# Microcontroller.net
KiCad netlist of a schematic drawn in Altium Designer
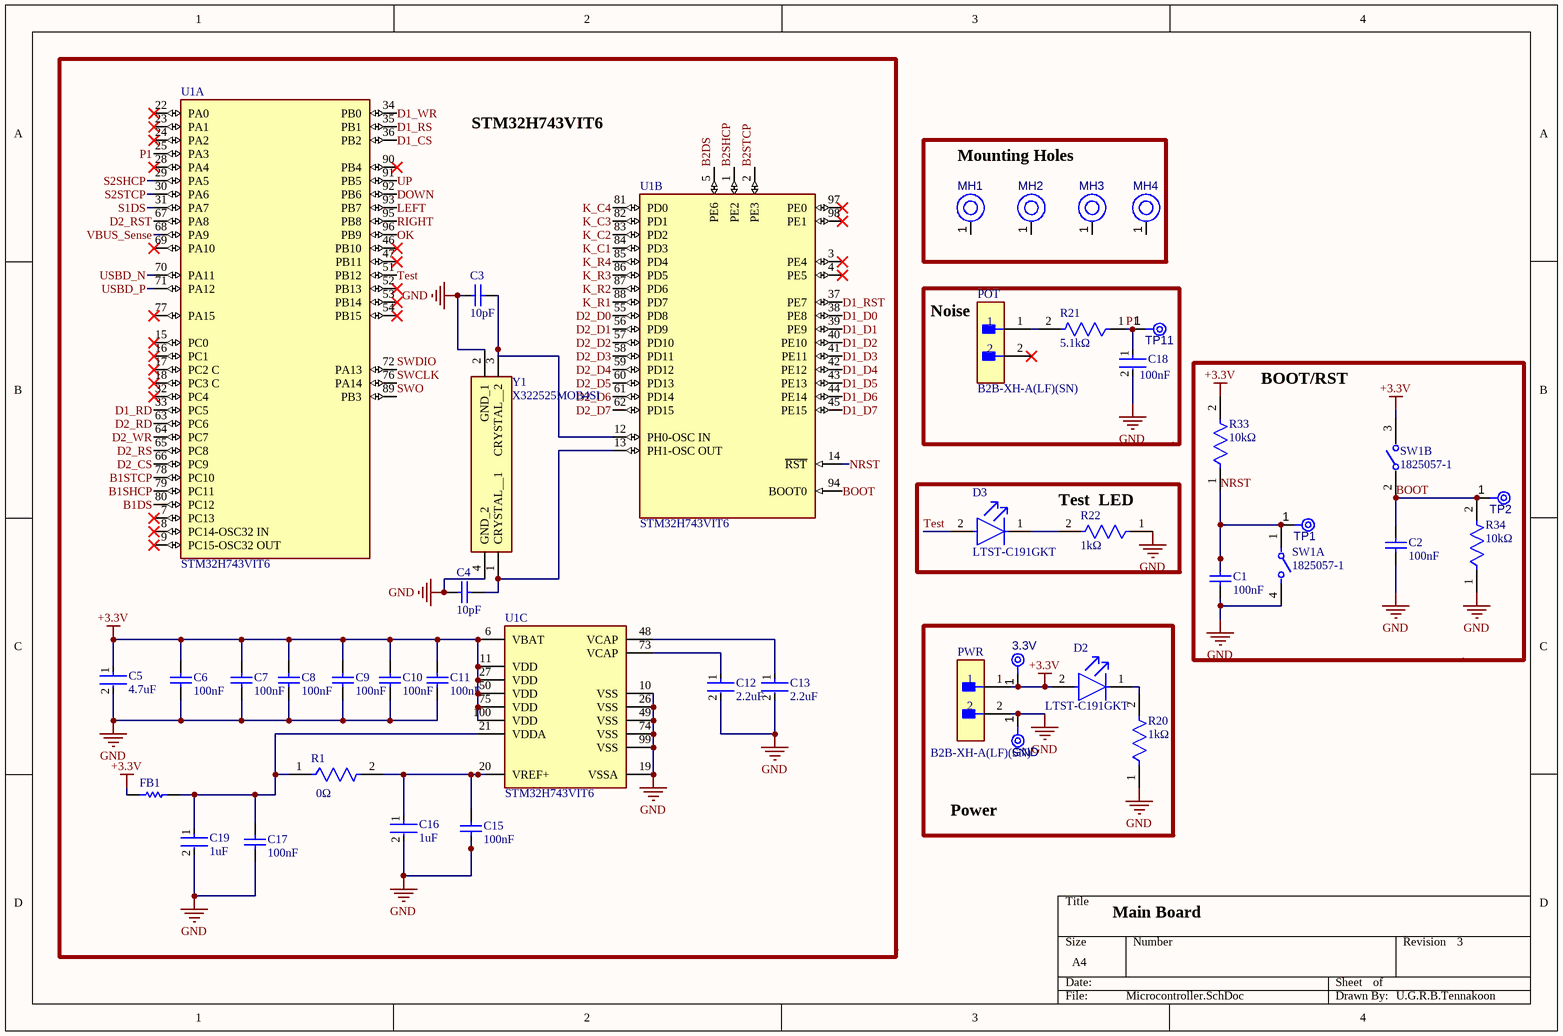
[diagram p0: Microcontroller.SchDoc]

(export (version "E")
  (design (tool "Eeschema 10.0.6"))
  (components
    (comp (ref "3.3V")
      (value "TPAD6R")
      (footprint "TP06R")
      (description "0.6mm round")
      (libsource (lib "ravindu tennakoon") (part "CMP-001-0001-4"))
    )
    (comp (ref "C1")
      (value "100nF")
      (footprint "CAPC1050X55X23ML05T13")
      (description "Chip Capacitor, 100 nF, +/- 10%, 16 V, -55 to 125 degC, 0402 (1005 Metric), RoHS, Tape and Reel")
      (fields (field (name "MANUFACTURER") "Samsung Electro-Mechanics"))
      (libsource (lib "Altium Content Vault") (part "CAP-NP-2"))
    )
    (comp (ref "C2")
      (value "100nF")
      (footprint "CAPC1050X55X23ML05T13")
      (description "Chip Capacitor, 100 nF, +/- 10%, 16 V, -55 to 125 degC, 0402 (1005 Metric), RoHS, Tape and Reel")
      (fields (field (name "MANUFACTURER") "Samsung Electro-Mechanics"))
      (libsource (lib "Altium Content Vault") (part "CAP-NP-2"))
    )
    (comp (ref "C3")
      (value "10pF")
      (footprint "CAPC1050X55X23ML05T13")
      (fields (field (name "MANUFACTURER") "Samsung Electro-Mechanics"))
      (libsource (lib "Altium Content Vault") (part "CAP-NP-2"))
    )
    (comp (ref "C4")
      (value "10pF")
      (footprint "CAPC1050X55X23ML05T13")
      (fields (field (name "MANUFACTURER") "Samsung Electro-Mechanics"))
      (libsource (lib "Altium Content Vault") (part "CAP-NP-2"))
    )
    (comp (ref "C5")
      (value "4.7uF")
      (footprint "FP-CC0603-DA-MFG")
      (description "CC0603KRX5R8BB475 CAP CER 4.7UF 25V X5R 0603")
      (fields
        (field (name "MANUFACTURER") "YAGEO")
        (field (name "MANUFACTURER PART NUMBER") "CC0603KRX5R8BB475")
      )
      (libsource (lib "Altium Content Vault") (part "11868f565c42a9108669ba33697ecf6"))
    )
    (comp (ref "C6")
      (value "100nF")
      (footprint "CAPC1050X55X23ML05T13")
      (fields (field (name "MANUFACTURER") "Samsung Electro-Mechanics"))
      (libsource (lib "Altium Content Vault") (part "CAP-NP-2"))
    )
    (comp (ref "C7")
      (value "100nF")
      (footprint "CAPC1050X55X23ML05T13")
      (description "Chip Capacitor, 100 nF, +/- 10%, 16 V, -55 to 125 degC, 0402 (1005 Metric), RoHS, Tape and Reel")
      (fields (field (name "MANUFACTURER") "Samsung Electro-Mechanics"))
      (libsource (lib "Altium Content Vault") (part "CAP-NP-2"))
    )
    (comp (ref "C8")
      (value "100nF")
      (footprint "CAPC1050X55X23ML05T13")
      (description "Chip Capacitor, 100 nF, +/- 10%, 16 V, -55 to 125 degC, 0402 (1005 Metric), RoHS, Tape and Reel")
      (fields (field (name "MANUFACTURER") "Samsung Electro-Mechanics"))
      (libsource (lib "Altium Content Vault") (part "CAP-NP-2"))
    )
    (comp (ref "C9")
      (value "100nF")
      (footprint "CAPC1050X55X23ML05T13")
      (description "Chip Capacitor, 100 nF, +/- 10%, 16 V, -55 to 125 degC, 0402 (1005 Metric), RoHS, Tape and Reel")
      (fields (field (name "MANUFACTURER") "Samsung Electro-Mechanics"))
      (libsource (lib "Altium Content Vault") (part "CAP-NP-2"))
    )
    (comp (ref "C10")
      (value "100nF")
      (footprint "CAPC1050X55X23ML05T13")
      (description "Chip Capacitor, 100 nF, +/- 10%, 16 V, -55 to 125 degC, 0402 (1005 Metric), RoHS, Tape and Reel")
      (fields (field (name "MANUFACTURER") "Samsung Electro-Mechanics"))
      (libsource (lib "Altium Content Vault") (part "CAP-NP-2"))
    )
    (comp (ref "C11")
      (value "100nF")
      (footprint "CAPC1050X55X23ML05T13")
      (description "Chip Capacitor, 100 nF, +/- 10%, 16 V, -55 to 125 degC, 0402 (1005 Metric), RoHS, Tape and Reel")
      (fields (field (name "MANUFACTURER") "Samsung Electro-Mechanics"))
      (libsource (lib "Altium Content Vault") (part "CAP-NP-2"))
    )
    (comp (ref "C12")
      (value "2.2uF")
      (footprint "FP-CL10-IPC_A")
      (description "CL10A225KO8NNNC Cap Ceramic 2.2uF 16V X5R ±10% Pad SMD 0603 +85°C T/R")
      (fields (field (name "TOLERANCE") "10%") (field (name "VOLTAGE") "16V"))
      (libsource (lib "Altium Content Vault") (part "b4654b650e69147ec39a6b967a45e02"))
    )
    (comp (ref "C13")
      (value "2.2uF")
      (footprint "FP-CL10-IPC_A")
      (description "CL10A225KO8NNNC Cap Ceramic 2.2uF 16V X5R ±10% Pad SMD 0603 +85°C T/R")
      (fields (field (name "TOLERANCE") "10%") (field (name "VOLTAGE") "16V"))
      (libsource (lib "Altium Content Vault") (part "b4654b650e69147ec39a6b967a45e02"))
    )
    (comp (ref "C15")
      (value "100nF")
      (footprint "CAPC1050X55X23ML05T13")
      (description "Chip Capacitor, 100 nF, +/- 10%, 16 V, -55 to 125 degC, 0402 (1005 Metric), RoHS, Tape and Reel")
      (fields (field (name "MANUFACTURER") "Samsung Electro-Mechanics"))
      (libsource (lib "Altium Content Vault") (part "CAP-NP-2"))
    )
    (comp (ref "C16")
      (value "1uF")
      (footprint "FP-CL10-IPC_A")
      (description "CL10A105KO8NNNC Cap Ceramic 1uF 16V X5R ±10% Pad SMD 0603 +85°C T/R")
      (fields (field (name "TOLERANCE") "10%") (field (name "VOLTAGE") "16V"))
      (libsource (lib "Altium Content Vault") (part "b4654b650e69147ec39a6b967a45e02"))
    )
    (comp (ref "C17")
      (value "100nF")
      (footprint "CAPC1050X55X23ML05T13")
      (description "Chip Capacitor, 100 nF, +/- 10%, 16 V, -55 to 125 degC, 0402 (1005 Metric), RoHS, Tape and Reel")
      (fields (field (name "MANUFACTURER") "Samsung Electro-Mechanics"))
      (libsource (lib "Altium Content Vault") (part "CAP-NP-2"))
    )
    (comp (ref "C18")
      (value "100nF")
      (footprint "FP-CL21-IPC_A")
      (description "CL21B104KCFWPNE CL21 Series 0805 100nF 100V ±10% Tolerance X7R Multilayer Ceramic Chip Capacitor")
      (fields (field (name "TOLERANCE") "10%"))
      (libsource (lib "Altium Content Vault") (part "b4654b650e69147ec39a6b967a45e02"))
    )
    (comp (ref "C19")
      (value "1uF")
      (footprint "FP-CL10-IPC_A")
      (description "CL10A105KO8NNNC Cap Ceramic 1uF 16V X5R ±10% Pad SMD 0603 +85°C T/R")
      (fields (field (name "TOLERANCE") "10%") (field (name "VOLTAGE") "16V"))
      (libsource (lib "Altium Content Vault") (part "b4654b650e69147ec39a6b967a45e02"))
    )
    (comp (ref "D2")
      (value "LTST-C191GKT")
      (footprint "FP-LTST-C191GKT-MFG")
      (description "LED GREEN CLEAR CHIP SMD")
      (libsource (lib "Altium Content Vault") (part "8706943c75ba83719d021d2fdc84c58"))
    )
    (comp (ref "D3")
      (value "LTST-C191GKT")
      (footprint "FP-LTST-C191GKT-MFG")
      (description "LED GREEN CLEAR CHIP SMD")
      (libsource (lib "Altium Content Vault") (part "8706943c75ba83719d021d2fdc84c58"))
    )
    (comp (ref "FB1")
      (value "~")
      (footprint "RESC1609X55X30LL10T20")
      (description "1206W4F0000T5E")
      (fields (field (name "PART NUMBER") "TNPU0603100RBZEN00") (field (name "MANUFACTURER") "Vishay Dale"))
      (libsource (lib "Altium Content Vault") (part "RES"))
    )
    (comp (ref "GND")
      (value "TPAD6R")
      (footprint "TP06R")
      (description "0.6mm round")
      (libsource (lib "ravindu tennakoon") (part "CMP-001-0001-4"))
    )
    (comp (ref "MH1")
      (value "PTH")
      (footprint "Copy of PTH-M2D5X5")
      (description "4mm, 3.2mm")
      (libsource (lib "ravindu tennakoon") (part "Copy of CMP-00028-00000-1"))
    )
    (comp (ref "MH2")
      (value "PTH")
      (footprint "Copy of PTH-M2D5X5")
      (description "4mm, 3.2mm")
      (libsource (lib "ravindu tennakoon") (part "Copy of CMP-00028-00000-1"))
    )
    (comp (ref "MH3")
      (value "PTH")
      (footprint "Copy of PTH-M2D5X5")
      (description "4mm, 3.2mm")
      (libsource (lib "ravindu tennakoon") (part "Copy of CMP-00028-00000-1"))
    )
    (comp (ref "MH4")
      (value "PTH")
      (footprint "Copy of PTH-M2D5X5")
      (description "4mm, 3.2mm")
      (libsource (lib "ravindu tennakoon") (part "Copy of CMP-00028-00000-1"))
    )
    (comp (ref "POT")
      (value "B2B-XH-A(LF)(SN)")
      (footprint "FP-B2B-XH-A_LF_SN-MFG")
      (description "CONN HEADER VERT 2POS 2.5MM")
      (libsource (lib "Altium Content Vault") (part "3bc925449376181038e59eaffc5286c"))
    )
    (comp (ref "PWR")
      (value "B2B-XH-A(LF)(SN)")
      (footprint "FP-B2B-XH-A_LF_SN-MFG")
      (description "CONN HEADER VERT 2POS 2.5MM")
      (libsource (lib "Altium Content Vault") (part "3bc925449376181038e59eaffc5286c"))
    )
    (comp (ref "R1")
      (value "0Ω")
      (footprint "FP-AC1206-MFG")
      (description "1206W4F0000T5E")
      (fields
        (field (name "MANUFACTURER PART NUMBER") "AC1206FR-07267RL")
        (field (name "OCTOPART") "https://octopart.com/ac1206fr-07267rl-yageo-71368055")
      )
      (libsource (lib "Altium Content Vault") (part "1029c3af85768c4190bb7ad29bc67b5"))
    )
    (comp (ref "R20")
      (value "1kΩ")
      (footprint "FP-SR0805-MFG")
      (description "RMC08051K5%N")
      (fields (field (name "MANUFACTURER PART NUMBER") "SR0805FR-4710KL") (field (name "TOLERANCE") "0.01"))
      (libsource (lib "Altium Content Vault") (part "1029c3af85768c4190bb7ad29bc67b5"))
    )
    (comp (ref "R21")
      (value "5.1kΩ")
      (footprint "FP-SR0805-MFG")
      (description "0805W8F1501T5E")
      (fields (field (name "MANUFACTURER PART NUMBER") "SR0805FR-4710KL") (field (name "TOLERANCE") "0.01"))
      (libsource (lib "Altium Content Vault") (part "1029c3af85768c4190bb7ad29bc67b5"))
    )
    (comp (ref "R22")
      (value "1kΩ")
      (footprint "FP-SR0805-MFG")
      (description "RMC08051K5%N")
      (fields (field (name "MANUFACTURER PART NUMBER") "SR0805FR-4710KL") (field (name "TOLERANCE") "0.01"))
      (libsource (lib "Altium Content Vault") (part "1029c3af85768c4190bb7ad29bc67b5"))
    )
    (comp (ref "R33")
      (value "10kΩ")
      (footprint "FP-SR0805-MFG")
      (description "RES SMD 0805 1/2W 1% 10K OHM")
      (fields (field (name "MANUFACTURER PART NUMBER") "SR0805FR-4710KL") (field (name "TOLERANCE") "0.01"))
      (libsource (lib "Altium Content Vault") (part "1029c3af85768c4190bb7ad29bc67b5"))
    )
    (comp (ref "R34")
      (value "10kΩ")
      (footprint "FP-SR0805-MFG")
      (description "RES SMD 0805 1/2W 1% 10K OHM")
      (fields (field (name "MANUFACTURER PART NUMBER") "SR0805FR-4710KL") (field (name "TOLERANCE") "0.01"))
      (libsource (lib "Altium Content Vault") (part "1029c3af85768c4190bb7ad29bc67b5"))
    )
    (comp (ref "SW1")
      (value "1825057-1")
      (footprint "FP-1825057-1-MFG")
      (description "SWITCH SLIDE DIP SPST 100MA 24V")
      (fields
        (field (name "OCTOPART") "https://octopart.com/1825057-1-te+connectivity-46507313")
        (field (name "MANUFACTURER") "TE Connectivity")
      )
      (libsource (lib "Altium Content Vault") (part "305b8df74c9585226458c49fb7f7021"))
    )
    (comp (ref "TP1")
      (value "TPAD6R")
      (footprint "TP06R")
      (description "0.6mm round")
      (libsource (lib "ravindu tennakoon") (part "CMP-001-0001-4"))
    )
    (comp (ref "TP2")
      (value "TPAD6R")
      (footprint "TP06R")
      (description "0.6mm round")
      (libsource (lib "ravindu tennakoon") (part "CMP-001-0001-4"))
    )
    (comp (ref "TP11")
      (value "TPAD6R")
      (footprint "TP06R")
      (description "0.6mm round")
      (libsource (lib "ravindu tennakoon") (part "CMP-001-0001-4"))
    )
    (comp (ref "U1")
      (value "STM32H743VIT6")
      (footprint "FP-LQFP100-1L-MFG")
      (description "IC MCU 32BIT 2MB FLASH 100LQFP")
      (fields
        (field (name "OCTOPART") "https://octopart.com/stm32h743vit6-stmicroelectronics-76372527")
        (field (name "MANUFACTURER") "STMicroelectronics")
      )
      (libsource (lib "") (part "01082ce2885d1d16a22823c45526fe6_2"))
    )
    (comp (ref "Y1")
      (value "X322525MOB4SI")
      (footprint "SamacSys:X322525MOB4SI")
      (description "Crystal or Oscillator")
      (libsource (lib "*") (part "X322525MOB4SI"))
    )
  )
  (nets
    (net (code "1") (name "+3.3V") (class "Default")
      (node (ref "3.3V") (pin "1") (pinfunction "TP_1") (pintype "passive"))
      (node (ref "C10") (pin "2") (pinfunction "2_2") (pintype "passive"))
      (node (ref "C11") (pin "2") (pinfunction "2_2") (pintype "passive"))
      (node (ref "C5") (pin "1") (pinfunction "1_1") (pintype "passive"))
      (node (ref "C6") (pin "2") (pinfunction "2_2") (pintype "passive"))
      (node (ref "C7") (pin "2") (pinfunction "2_2") (pintype "passive"))
      (node (ref "C8") (pin "2") (pinfunction "2_2") (pintype "passive"))
      (node (ref "C9") (pin "2") (pinfunction "2_2") (pintype "passive"))
      (node (ref "D2") (pin "2") (pinfunction "A_2") (pintype "passive"))
      (node (ref "FB1") (pin "1") (pinfunction "1_1") (pintype "passive"))
      (node (ref "PWR") (pin "1") (pinfunction "1_1") (pintype "passive"))
      (node (ref "R33") (pin "2") (pinfunction "2_2") (pintype "passive"))
      (node (ref "SW1") (pin "3") (pinfunction "3_3") (pintype "passive"))
      (node (ref "U1") (pin "100") (pinfunction "VDD_100") (pintype "power_in"))
      (node (ref "U1") (pin "11") (pinfunction "VDD_11") (pintype "power_in"))
      (node (ref "U1") (pin "27") (pinfunction "VDD_27") (pintype "power_in"))
      (node (ref "U1") (pin "50") (pinfunction "VDD_50") (pintype "power_in"))
      (node (ref "U1") (pin "6") (pinfunction "VBAT_6") (pintype "power_in"))
      (node (ref "U1") (pin "75") (pinfunction "VDD_75") (pintype "power_in"))
    )
    (net (code "2") (name "/B1DS") (class "Default")
      (node (ref "U1") (pin "80") (pinfunction "PC12_80") (pintype "bidirectional"))
    )
    (net (code "3") (name "/B1SHCP") (class "Default")
      (node (ref "U1") (pin "79") (pinfunction "PC11_79") (pintype "bidirectional"))
    )
    (net (code "4") (name "/B1STCP") (class "Default")
      (node (ref "U1") (pin "78") (pinfunction "PC10_78") (pintype "bidirectional"))
    )
    (net (code "5") (name "/B2DS") (class "Default")
      (node (ref "U1") (pin "5") (pinfunction "PE6_5") (pintype "bidirectional"))
    )
    (net (code "6") (name "/B2SHCP") (class "Default")
      (node (ref "U1") (pin "1") (pinfunction "PE2_1") (pintype "bidirectional"))
    )
    (net (code "7") (name "/B2STCP") (class "Default")
      (node (ref "U1") (pin "2") (pinfunction "PE3_2") (pintype "bidirectional"))
    )
    (net (code "8") (name "/BOOT") (class "Default")
      (node (ref "C2") (pin "2") (pinfunction "2_2") (pintype "passive"))
      (node (ref "R34") (pin "2") (pinfunction "2_2") (pintype "passive"))
      (node (ref "SW1") (pin "2") (pinfunction "2_2") (pintype "passive"))
      (node (ref "TP2") (pin "1") (pinfunction "TP_1") (pintype "passive"))
      (node (ref "U1") (pin "94") (pinfunction "BOOT0_94") (pintype "input"))
    )
    (net (code "9") (name "/D1_CS") (class "Default")
      (node (ref "U1") (pin "36") (pinfunction "PB2_36") (pintype "bidirectional"))
    )
    (net (code "10") (name "/D1_D0") (class "Default")
      (node (ref "U1") (pin "38") (pinfunction "PE8_38") (pintype "bidirectional"))
    )
    (net (code "11") (name "/D1_D1") (class "Default")
      (node (ref "U1") (pin "39") (pinfunction "PE9_39") (pintype "bidirectional"))
    )
    (net (code "12") (name "/D1_D2") (class "Default")
      (node (ref "U1") (pin "40") (pinfunction "PE10_40") (pintype "bidirectional"))
    )
    (net (code "13") (name "/D1_D3") (class "Default")
      (node (ref "U1") (pin "41") (pinfunction "PE11_41") (pintype "bidirectional"))
    )
    (net (code "14") (name "/D1_D4") (class "Default")
      (node (ref "U1") (pin "42") (pinfunction "PE12_42") (pintype "bidirectional"))
    )
    (net (code "15") (name "/D1_D5") (class "Default")
      (node (ref "U1") (pin "43") (pinfunction "PE13_43") (pintype "bidirectional"))
    )
    (net (code "16") (name "/D1_D6") (class "Default")
      (node (ref "U1") (pin "44") (pinfunction "PE14_44") (pintype "bidirectional"))
    )
    (net (code "17") (name "/D1_D7") (class "Default")
      (node (ref "U1") (pin "45") (pinfunction "PE15_45") (pintype "bidirectional"))
    )
    (net (code "18") (name "/D1_RD") (class "Default")
      (node (ref "U1") (pin "33") (pinfunction "PC5_33") (pintype "bidirectional"))
    )
    (net (code "19") (name "/D1_RS") (class "Default")
      (node (ref "U1") (pin "35") (pinfunction "PB1_35") (pintype "bidirectional"))
    )
    (net (code "20") (name "/D1_RST") (class "Default")
      (node (ref "U1") (pin "37") (pinfunction "PE7_37") (pintype "bidirectional"))
    )
    (net (code "21") (name "/D1_WR") (class "Default")
      (node (ref "U1") (pin "34") (pinfunction "PB0_34") (pintype "bidirectional"))
    )
    (net (code "22") (name "/D2_CS") (class "Default")
      (node (ref "U1") (pin "66") (pinfunction "PC9_66") (pintype "bidirectional"))
    )
    (net (code "23") (name "/D2_D0") (class "Default")
      (node (ref "U1") (pin "55") (pinfunction "PD8_55") (pintype "bidirectional"))
    )
    (net (code "24") (name "/D2_D1") (class "Default")
      (node (ref "U1") (pin "56") (pinfunction "PD9_56") (pintype "bidirectional"))
    )
    (net (code "25") (name "/D2_D2") (class "Default")
      (node (ref "U1") (pin "57") (pinfunction "PD10_57") (pintype "bidirectional"))
    )
    (net (code "26") (name "/D2_D3") (class "Default")
      (node (ref "U1") (pin "58") (pinfunction "PD11_58") (pintype "bidirectional"))
    )
    (net (code "27") (name "/D2_D4") (class "Default")
      (node (ref "U1") (pin "59") (pinfunction "PD12_59") (pintype "bidirectional"))
    )
    (net (code "28") (name "/D2_D5") (class "Default")
      (node (ref "U1") (pin "60") (pinfunction "PD13_60") (pintype "bidirectional"))
    )
    (net (code "29") (name "/D2_D6") (class "Default")
      (node (ref "U1") (pin "61") (pinfunction "PD14_61") (pintype "bidirectional"))
    )
    (net (code "30") (name "/D2_D7") (class "Default")
      (node (ref "U1") (pin "62") (pinfunction "PD15_62") (pintype "bidirectional"))
    )
    (net (code "31") (name "/D2_RD") (class "Default")
      (node (ref "U1") (pin "63") (pinfunction "PC6_63") (pintype "bidirectional"))
    )
    (net (code "32") (name "/D2_RS") (class "Default")
      (node (ref "U1") (pin "65") (pinfunction "PC8_65") (pintype "bidirectional"))
    )
    (net (code "33") (name "/D2_RST") (class "Default")
      (node (ref "U1") (pin "67") (pinfunction "PA8_67") (pintype "bidirectional"))
    )
    (net (code "34") (name "/D2_WR") (class "Default")
      (node (ref "U1") (pin "64") (pinfunction "PC7_64") (pintype "bidirectional"))
    )
    (net (code "35") (name "/DOWN") (class "Default")
      (node (ref "U1") (pin "92") (pinfunction "PB6_92") (pintype "bidirectional"))
    )
    (net (code "36") (name "/K_C1") (class "Default")
      (node (ref "U1") (pin "84") (pinfunction "PD3_84") (pintype "bidirectional"))
    )
    (net (code "37") (name "/K_C2") (class "Default")
      (node (ref "U1") (pin "83") (pinfunction "PD2_83") (pintype "bidirectional"))
    )
    (net (code "38") (name "/K_C3") (class "Default")
      (node (ref "U1") (pin "82") (pinfunction "PD1_82") (pintype "bidirectional"))
    )
    (net (code "39") (name "/K_C4") (class "Default")
      (node (ref "U1") (pin "81") (pinfunction "PD0_81") (pintype "bidirectional"))
    )
    (net (code "40") (name "/K_R1") (class "Default")
      (node (ref "U1") (pin "88") (pinfunction "PD7_88") (pintype "bidirectional"))
    )
    (net (code "41") (name "/K_R2") (class "Default")
      (node (ref "U1") (pin "87") (pinfunction "PD6_87") (pintype "bidirectional"))
    )
    (net (code "42") (name "/K_R3") (class "Default")
      (node (ref "U1") (pin "86") (pinfunction "PD5_86") (pintype "bidirectional"))
    )
    (net (code "43") (name "/K_R4") (class "Default")
      (node (ref "U1") (pin "85") (pinfunction "PD4_85") (pintype "bidirectional"))
    )
    (net (code "44") (name "/LEFT") (class "Default")
      (node (ref "U1") (pin "93") (pinfunction "PB7_93") (pintype "bidirectional"))
    )
    (net (code "45") (name "/NRST") (class "Default")
      (node (ref "C1") (pin "2") (pinfunction "2_2") (pintype "passive"))
      (node (ref "R33") (pin "1") (pinfunction "1_1") (pintype "passive"))
      (node (ref "SW1") (pin "1") (pinfunction "1_1") (pintype "passive"))
      (node (ref "TP1") (pin "1") (pinfunction "TP_1") (pintype "passive"))
      (node (ref "U1") (pin "14") (pinfunction "~{RST}_14") (pintype "input"))
    )
    (net (code "46") (name "/OK") (class "Default")
      (node (ref "U1") (pin "96") (pinfunction "PB9_96") (pintype "bidirectional"))
    )
    (net (code "47") (name "/P1") (class "Default")
      (node (ref "C18") (pin "1") (pinfunction "1_1") (pintype "passive"))
      (node (ref "R21") (pin "1") (pinfunction "1_1") (pintype "passive"))
      (node (ref "TP11") (pin "1") (pinfunction "TP_1") (pintype "passive"))
      (node (ref "U1") (pin "25") (pinfunction "PA3_25") (pintype "bidirectional"))
    )
    (net (code "48") (name "/RIGHT") (class "Default")
      (node (ref "U1") (pin "95") (pinfunction "PB8_95") (pintype "bidirectional"))
    )
    (net (code "49") (name "/S1DS") (class "Default")
      (node (ref "U1") (pin "31") (pinfunction "PA7_31") (pintype "bidirectional"))
    )
    (net (code "50") (name "/S2SHCP") (class "Default")
      (node (ref "U1") (pin "29") (pinfunction "PA5_29") (pintype "bidirectional"))
    )
    (net (code "51") (name "/S2STCP") (class "Default")
      (node (ref "U1") (pin "30") (pinfunction "PA6_30") (pintype "bidirectional"))
    )
    (net (code "52") (name "/SWCLK") (class "Default")
      (node (ref "U1") (pin "76") (pinfunction "PA14_76") (pintype "bidirectional"))
    )
    (net (code "53") (name "/SWDIO") (class "Default")
      (node (ref "U1") (pin "72") (pinfunction "PA13_72") (pintype "bidirectional"))
    )
    (net (code "54") (name "/SWO") (class "Default")
      (node (ref "U1") (pin "89") (pinfunction "PB3_89") (pintype "bidirectional"))
    )
    (net (code "55") (name "/Test") (class "Default")
      (node (ref "D3") (pin "2") (pinfunction "A_2") (pintype "passive"))
      (node (ref "U1") (pin "51") (pinfunction "PB12_51") (pintype "bidirectional"))
    )
    (net (code "56") (name "/UP") (class "Default")
      (node (ref "U1") (pin "91") (pinfunction "PB5_91") (pintype "bidirectional"))
    )
    (net (code "57") (name "/USBD_N") (class "Default")
      (node (ref "U1") (pin "70") (pinfunction "PA11_70") (pintype "bidirectional"))
    )
    (net (code "58") (name "/USBD_P") (class "Default")
      (node (ref "U1") (pin "71") (pinfunction "PA12_71") (pintype "bidirectional"))
    )
    (net (code "59") (name "/VBUS_Sense") (class "Default")
      (node (ref "U1") (pin "68") (pinfunction "PA9_68") (pintype "bidirectional"))
    )
    (net (code "60") (name "GND") (class "Default")
      (node (ref "C1") (pin "1") (pinfunction "1_1") (pintype "passive"))
      (node (ref "C10") (pin "1") (pinfunction "1_1") (pintype "passive"))
      (node (ref "C11") (pin "1") (pinfunction "1_1") (pintype "passive"))
      (node (ref "C12") (pin "2") (pinfunction "2_2") (pintype "passive"))
      (node (ref "C13") (pin "2") (pinfunction "2_2") (pintype "passive"))
      (node (ref "C15") (pin "1") (pinfunction "1_1") (pintype "passive"))
      (node (ref "C16") (pin "2") (pinfunction "2_2") (pintype "passive"))
      (node (ref "C17") (pin "1") (pinfunction "1_1") (pintype "passive"))
      (node (ref "C18") (pin "2") (pinfunction "2_2") (pintype "passive"))
      (node (ref "C19") (pin "2") (pinfunction "2_2") (pintype "passive"))
      (node (ref "C2") (pin "1") (pinfunction "1_1") (pintype "passive"))
      (node (ref "C3") (pin "2") (pinfunction "2_2") (pintype "passive"))
      (node (ref "C4") (pin "1") (pinfunction "1_1") (pintype "passive"))
      (node (ref "C5") (pin "2") (pinfunction "2_2") (pintype "passive"))
      (node (ref "C6") (pin "1") (pinfunction "1_1") (pintype "passive"))
      (node (ref "C7") (pin "1") (pinfunction "1_1") (pintype "passive"))
      (node (ref "C8") (pin "1") (pinfunction "1_1") (pintype "passive"))
      (node (ref "C9") (pin "1") (pinfunction "1_1") (pintype "passive"))
      (node (ref "GND") (pin "1") (pinfunction "TP_1") (pintype "passive"))
      (node (ref "PWR") (pin "2") (pinfunction "2_2") (pintype "passive"))
      (node (ref "R20") (pin "1") (pinfunction "1_1") (pintype "passive"))
      (node (ref "R22") (pin "1") (pinfunction "1_1") (pintype "passive"))
      (node (ref "R34") (pin "1") (pinfunction "1_1") (pintype "passive"))
      (node (ref "SW1") (pin "4") (pinfunction "4_4") (pintype "passive"))
      (node (ref "U1") (pin "10") (pinfunction "VSS_10") (pintype "power_in"))
      (node (ref "U1") (pin "19") (pinfunction "VSSA_19") (pintype "power_in"))
      (node (ref "U1") (pin "26") (pinfunction "VSS_26") (pintype "power_in"))
      (node (ref "U1") (pin "49") (pinfunction "VSS_49") (pintype "power_in"))
      (node (ref "U1") (pin "74") (pinfunction "VSS_74") (pintype "power_in"))
      (node (ref "U1") (pin "99") (pinfunction "VSS_99") (pintype "power_in"))
      (node (ref "Y1") (pin "2") (pinfunction "GND_1_2") (pintype "passive"))
      (node (ref "Y1") (pin "4") (pinfunction "GND_2_4") (pintype "passive"))
    )
    (net (code "61") (name "Net-(C12-Pad1)") (class "Default")
      (node (ref "C12") (pin "1") (pinfunction "1_1") (pintype "passive"))
      (node (ref "U1") (pin "73") (pinfunction "VCAP_73") (pintype "passive"))
    )
    (net (code "62") (name "Net-(C13-Pad1)") (class "Default")
      (node (ref "C13") (pin "1") (pinfunction "1_1") (pintype "passive"))
      (node (ref "U1") (pin "48") (pinfunction "VCAP_48") (pintype "passive"))
    )
    (net (code "63") (name "Net-(D2-C)") (class "Default")
      (node (ref "D2") (pin "1") (pinfunction "C_1") (pintype "passive"))
      (node (ref "R20") (pin "2") (pinfunction "2_2") (pintype "passive"))
    )
    (net (code "64") (name "Net-(D3-C)") (class "Default")
      (node (ref "D3") (pin "1") (pinfunction "C_1") (pintype "passive"))
      (node (ref "R22") (pin "2") (pinfunction "2_2") (pintype "passive"))
    )
    (net (code "65") (name "Net-(POT-Pad1)") (class "Default")
      (node (ref "POT") (pin "1") (pinfunction "1_1") (pintype "passive"))
      (node (ref "R21") (pin "2") (pinfunction "2_2") (pintype "passive"))
    )
    (net (code "66") (name "Net-(U1B-PH0-OSC_IN)") (class "Default")
      (node (ref "C3") (pin "1") (pinfunction "1_1") (pintype "passive"))
      (node (ref "U1") (pin "12") (pinfunction "PH0-OSC_IN_12") (pintype "bidirectional"))
      (node (ref "Y1") (pin "3") (pinfunction "CRYSTAL__2_3") (pintype "passive"))
    )
    (net (code "67") (name "Net-(U1B-PH1-OSC_OUT)") (class "Default")
      (node (ref "C4") (pin "2") (pinfunction "2_2") (pintype "passive"))
      (node (ref "U1") (pin "13") (pinfunction "PH1-OSC_OUT_13") (pintype "bidirectional"))
      (node (ref "Y1") (pin "1") (pinfunction "CRYSTAL__1_1") (pintype "passive"))
    )
    (net (code "68") (name "Net-(U1C-VDDA)") (class "Default")
      (node (ref "C17") (pin "2") (pinfunction "2_2") (pintype "passive"))
      (node (ref "C19") (pin "1") (pinfunction "1_1") (pintype "passive"))
      (node (ref "FB1") (pin "2") (pinfunction "2_2") (pintype "passive"))
      (node (ref "R1") (pin "1") (pinfunction "1_1") (pintype "passive"))
      (node (ref "U1") (pin "21") (pinfunction "VDDA_21") (pintype "power_in"))
    )
    (net (code "69") (name "Net-(U1C-VREF+)") (class "Default")
      (node (ref "C15") (pin "2") (pinfunction "2_2") (pintype "passive"))
      (node (ref "C16") (pin "1") (pinfunction "1_1") (pintype "passive"))
      (node (ref "R1") (pin "2") (pinfunction "2_2") (pintype "passive"))
      (node (ref "U1") (pin "20") (pinfunction "VREF+_20") (pintype "power_in"))
    )
    (net (code "70") (name "unconnected-(MH1-H1-Pad1)") (class "Default")
      (node (ref "MH1") (pin "1") (pinfunction "H1_1") (pintype "passive"))
    )
    (net (code "71") (name "unconnected-(MH2-H1-Pad1)") (class "Default")
      (node (ref "MH2") (pin "1") (pinfunction "H1_1") (pintype "passive"))
    )
    (net (code "72") (name "unconnected-(MH3-H1-Pad1)") (class "Default")
      (node (ref "MH3") (pin "1") (pinfunction "H1_1") (pintype "passive"))
    )
    (net (code "73") (name "unconnected-(MH4-H1-Pad1)") (class "Default")
      (node (ref "MH4") (pin "1") (pinfunction "H1_1") (pintype "passive"))
    )
    (net (code "74") (name "unconnected-(POT-Pad2)") (class "Default")
      (node (ref "POT") (pin "2") (pinfunction "2_2") (pintype "passive+no_connect"))
    )
    (net (code "75") (name "unconnected-(U1A-PA0-Pad22)") (class "Default")
      (node (ref "U1") (pin "22") (pinfunction "PA0_22") (pintype "bidirectional+no_connect"))
    )
    (net (code "76") (name "unconnected-(U1A-PA1-Pad23)") (class "Default")
      (node (ref "U1") (pin "23") (pinfunction "PA1_23") (pintype "bidirectional+no_connect"))
    )
    (net (code "77") (name "unconnected-(U1A-PA2-Pad24)") (class "Default")
      (node (ref "U1") (pin "24") (pinfunction "PA2_24") (pintype "bidirectional+no_connect"))
    )
    (net (code "78") (name "unconnected-(U1A-PA4-Pad28)") (class "Default")
      (node (ref "U1") (pin "28") (pinfunction "PA4_28") (pintype "bidirectional+no_connect"))
    )
    (net (code "79") (name "unconnected-(U1A-PA10-Pad69)") (class "Default")
      (node (ref "U1") (pin "69") (pinfunction "PA10_69") (pintype "bidirectional+no_connect"))
    )
    (net (code "80") (name "unconnected-(U1A-PA15-Pad77)") (class "Default")
      (node (ref "U1") (pin "77") (pinfunction "PA15_77") (pintype "bidirectional+no_connect"))
    )
    (net (code "81") (name "unconnected-(U1A-PB4-Pad90)") (class "Default")
      (node (ref "U1") (pin "90") (pinfunction "PB4_90") (pintype "bidirectional+no_connect"))
    )
    (net (code "82") (name "unconnected-(U1A-PB10-Pad46)") (class "Default")
      (node (ref "U1") (pin "46") (pinfunction "PB10_46") (pintype "bidirectional+no_connect"))
    )
    (net (code "83") (name "unconnected-(U1A-PB11-Pad47)") (class "Default")
      (node (ref "U1") (pin "47") (pinfunction "PB11_47") (pintype "bidirectional+no_connect"))
    )
    (net (code "84") (name "unconnected-(U1A-PB13-Pad52)") (class "Default")
      (node (ref "U1") (pin "52") (pinfunction "PB13_52") (pintype "bidirectional+no_connect"))
    )
    (net (code "85") (name "unconnected-(U1A-PB14-Pad53)") (class "Default")
      (node (ref "U1") (pin "53") (pinfunction "PB14_53") (pintype "bidirectional+no_connect"))
    )
    (net (code "86") (name "unconnected-(U1A-PB15-Pad54)") (class "Default")
      (node (ref "U1") (pin "54") (pinfunction "PB15_54") (pintype "bidirectional+no_connect"))
    )
    (net (code "87") (name "unconnected-(U1A-PC0-Pad15)") (class "Default")
      (node (ref "U1") (pin "15") (pinfunction "PC0_15") (pintype "bidirectional+no_connect"))
    )
    (net (code "88") (name "unconnected-(U1A-PC1-Pad16)") (class "Default")
      (node (ref "U1") (pin "16") (pinfunction "PC1_16") (pintype "bidirectional+no_connect"))
    )
    (net (code "89") (name "unconnected-(U1A-PC2_C-Pad17)") (class "Default")
      (node (ref "U1") (pin "17") (pinfunction "PC2_C_17") (pintype "bidirectional+no_connect"))
    )
    (net (code "90") (name "unconnected-(U1A-PC3_C-Pad18)") (class "Default")
      (node (ref "U1") (pin "18") (pinfunction "PC3_C_18") (pintype "bidirectional+no_connect"))
    )
    (net (code "91") (name "unconnected-(U1A-PC4-Pad32)") (class "Default")
      (node (ref "U1") (pin "32") (pinfunction "PC4_32") (pintype "bidirectional+no_connect"))
    )
    (net (code "92") (name "unconnected-(U1A-PC13-Pad7)") (class "Default")
      (node (ref "U1") (pin "7") (pinfunction "PC13_7") (pintype "bidirectional+no_connect"))
    )
    (net (code "93") (name "unconnected-(U1A-PC14-OSC32_IN-Pad8)") (class "Default")
      (node (ref "U1") (pin "8") (pinfunction "PC14-OSC32_IN_8") (pintype "bidirectional+no_connect"))
    )
    (net (code "94") (name "unconnected-(U1A-PC15-OSC32_OUT-Pad9)") (class "Default")
      (node (ref "U1") (pin "9") (pinfunction "PC15-OSC32_OUT_9") (pintype "bidirectional+no_connect"))
    )
    (net (code "95") (name "unconnected-(U1B-PE0-Pad97)") (class "Default")
      (node (ref "U1") (pin "97") (pinfunction "PE0_97") (pintype "bidirectional+no_connect"))
    )
    (net (code "96") (name "unconnected-(U1B-PE1-Pad98)") (class "Default")
      (node (ref "U1") (pin "98") (pinfunction "PE1_98") (pintype "bidirectional+no_connect"))
    )
    (net (code "97") (name "unconnected-(U1B-PE4-Pad3)") (class "Default")
      (node (ref "U1") (pin "3") (pinfunction "PE4_3") (pintype "bidirectional+no_connect"))
    )
    (net (code "98") (name "unconnected-(U1B-PE5-Pad4)") (class "Default")
      (node (ref "U1") (pin "4") (pinfunction "PE5_4") (pintype "bidirectional+no_connect"))
    )
  )
)
